# neural_network.net
KiCad netlist of a schematic drawn in EAGLE
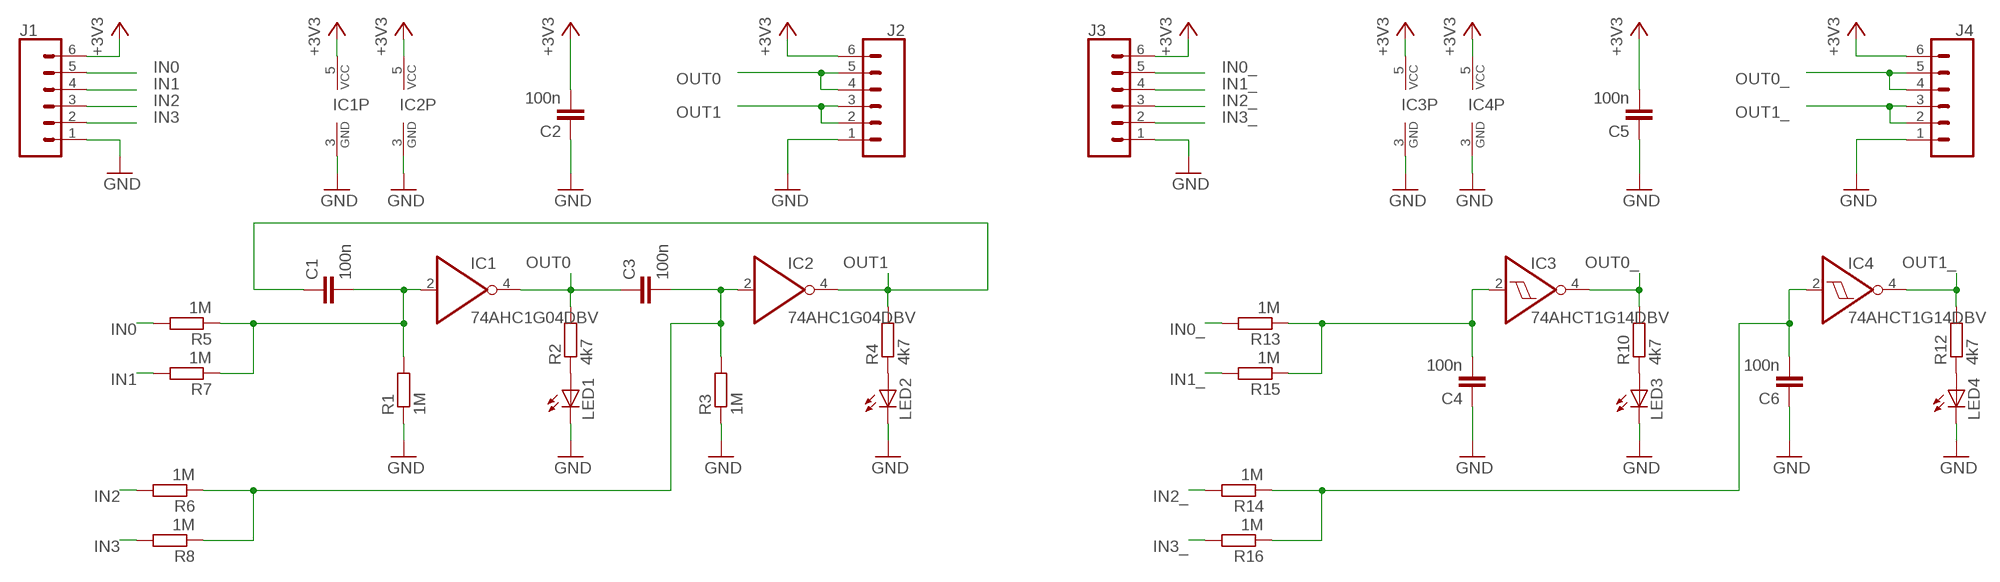
[diagram p0: schematic, sheet 1]

(export (version "E")
  (design (tool "Eeschema 10.0.6"))
  (components
    (comp (ref "C1")
      (value "100n")
      (footprint "eagle-import:C0805")
      (libsource (lib "eagle-import") (part "C-EUC0805"))
    )
    (comp (ref "C2")
      (value "100n")
      (footprint "eagle-import:C0805")
      (libsource (lib "eagle-import") (part "C-EUC0805"))
    )
    (comp (ref "C3")
      (value "100n")
      (footprint "eagle-import:C0805")
      (libsource (lib "eagle-import") (part "C-EUC0805"))
    )
    (comp (ref "C4")
      (value "100n")
      (footprint "eagle-import:C0805")
      (libsource (lib "eagle-import") (part "C-EUC0805"))
    )
    (comp (ref "C5")
      (value "100n")
      (footprint "eagle-import:C0805")
      (libsource (lib "eagle-import") (part "C-EUC0805"))
    )
    (comp (ref "C6")
      (value "100n")
      (footprint "eagle-import:C0805")
      (libsource (lib "eagle-import") (part "C-EUC0805"))
    )
    (comp (ref "IC1")
      (value "74AHC1G04DBV")
      (footprint "eagle-import:SOT23-5")
      (libsource (lib "eagle-import") (part "741G04DBVAHC"))
    )
    (comp (ref "IC2")
      (value "74AHC1G04DBV")
      (footprint "eagle-import:SOT23-5")
      (libsource (lib "eagle-import") (part "741G04DBVAHC"))
    )
    (comp (ref "IC3")
      (value "74AHCT1G14DBV")
      (footprint "eagle-import:SOT23-5")
      (libsource (lib "eagle-import") (part "741G14DBVAHCT"))
    )
    (comp (ref "IC4")
      (value "74AHCT1G14DBV")
      (footprint "eagle-import:SOT23-5")
      (libsource (lib "eagle-import") (part "741G14DBVAHCT"))
    )
    (comp (ref "J1")
      (value "CONN_06LONGPADS")
      (footprint "eagle-import:1X06_LONGPADS")
      (libsource (lib "eagle-import") (part "CONN_06LONGPADS"))
    )
    (comp (ref "J2")
      (value "CONN_06LONGPADS")
      (footprint "eagle-import:1X06_LONGPADS")
      (libsource (lib "eagle-import") (part "CONN_06LONGPADS"))
    )
    (comp (ref "J3")
      (value "CONN_06LONGPADS")
      (footprint "eagle-import:1X06_LONGPADS")
      (libsource (lib "eagle-import") (part "CONN_06LONGPADS"))
    )
    (comp (ref "J4")
      (value "CONN_06LONGPADS")
      (footprint "eagle-import:1X06_LONGPADS")
      (libsource (lib "eagle-import") (part "CONN_06LONGPADS"))
    )
    (comp (ref "LED1")
      (value "LEDCHIPLED_1206")
      (footprint "eagle-import:CHIPLED_1206")
      (libsource (lib "eagle-import") (part "LEDCHIPLED_1206"))
    )
    (comp (ref "LED2")
      (value "LEDCHIPLED_1206")
      (footprint "eagle-import:CHIPLED_1206")
      (libsource (lib "eagle-import") (part "LEDCHIPLED_1206"))
    )
    (comp (ref "LED3")
      (value "LEDCHIPLED_1206")
      (footprint "eagle-import:CHIPLED_1206")
      (libsource (lib "eagle-import") (part "LEDCHIPLED_1206"))
    )
    (comp (ref "LED4")
      (value "LEDCHIPLED_1206")
      (footprint "eagle-import:CHIPLED_1206")
      (libsource (lib "eagle-import") (part "LEDCHIPLED_1206"))
    )
    (comp (ref "R1")
      (value "1M")
      (footprint "eagle-import:M0805")
      (libsource (lib "eagle-import") (part "R-EU_M0805"))
    )
    (comp (ref "R2")
      (value "4k7")
      (footprint "eagle-import:M0805")
      (libsource (lib "eagle-import") (part "R-EU_M0805"))
    )
    (comp (ref "R3")
      (value "1M")
      (footprint "eagle-import:M0805")
      (libsource (lib "eagle-import") (part "R-EU_M0805"))
    )
    (comp (ref "R4")
      (value "4k7")
      (footprint "eagle-import:M0805")
      (libsource (lib "eagle-import") (part "R-EU_M0805"))
    )
    (comp (ref "R5")
      (value "1M")
      (footprint "eagle-import:M0805")
      (libsource (lib "eagle-import") (part "R-EU_M0805"))
    )
    (comp (ref "R6")
      (value "1M")
      (footprint "eagle-import:M0805")
      (libsource (lib "eagle-import") (part "R-EU_M0805"))
    )
    (comp (ref "R7")
      (value "1M")
      (footprint "eagle-import:M0805")
      (libsource (lib "eagle-import") (part "R-EU_M0805"))
    )
    (comp (ref "R8")
      (value "1M")
      (footprint "eagle-import:M0805")
      (libsource (lib "eagle-import") (part "R-EU_M0805"))
    )
    (comp (ref "R10")
      (value "4k7")
      (footprint "eagle-import:M0805")
      (libsource (lib "eagle-import") (part "R-EU_M0805"))
    )
    (comp (ref "R12")
      (value "4k7")
      (footprint "eagle-import:M0805")
      (libsource (lib "eagle-import") (part "R-EU_M0805"))
    )
    (comp (ref "R13")
      (value "1M")
      (footprint "eagle-import:M0805")
      (libsource (lib "eagle-import") (part "R-EU_M0805"))
    )
    (comp (ref "R14")
      (value "1M")
      (footprint "eagle-import:M0805")
      (libsource (lib "eagle-import") (part "R-EU_M0805"))
    )
    (comp (ref "R15")
      (value "1M")
      (footprint "eagle-import:M0805")
      (libsource (lib "eagle-import") (part "R-EU_M0805"))
    )
    (comp (ref "R16")
      (value "1M")
      (footprint "eagle-import:M0805")
      (libsource (lib "eagle-import") (part "R-EU_M0805"))
    )
  )
  (nets
    (net (code "1") (name "+3V3") (class "Default")
      (node (ref "C2") (pin "2") (pinfunction "2_2") (pintype "passive"))
      (node (ref "C5") (pin "2") (pinfunction "2_2") (pintype "passive"))
      (node (ref "IC1") (pin "5") (pinfunction "VCC_5") (pintype "power_in"))
      (node (ref "IC2") (pin "5") (pinfunction "VCC_5") (pintype "power_in"))
      (node (ref "IC3") (pin "5") (pinfunction "VCC_5") (pintype "power_in"))
      (node (ref "IC4") (pin "5") (pinfunction "VCC_5") (pintype "power_in"))
      (node (ref "J1") (pin "6") (pinfunction "6_6") (pintype "passive"))
      (node (ref "J2") (pin "6") (pinfunction "6_6") (pintype "passive"))
      (node (ref "J3") (pin "6") (pinfunction "6_6") (pintype "passive"))
      (node (ref "J4") (pin "6") (pinfunction "6_6") (pintype "passive"))
    )
    (net (code "2") (name "/IN0") (class "Default")
      (node (ref "J1") (pin "5") (pinfunction "5_5") (pintype "passive"))
      (node (ref "R5") (pin "2") (pinfunction "2_2") (pintype "passive"))
    )
    (net (code "3") (name "/IN0_") (class "Default")
      (node (ref "J3") (pin "5") (pinfunction "5_5") (pintype "passive"))
      (node (ref "R13") (pin "2") (pinfunction "2_2") (pintype "passive"))
    )
    (net (code "4") (name "/IN1") (class "Default")
      (node (ref "J1") (pin "4") (pinfunction "4_4") (pintype "passive"))
      (node (ref "R7") (pin "2") (pinfunction "2_2") (pintype "passive"))
    )
    (net (code "5") (name "/IN1_") (class "Default")
      (node (ref "J3") (pin "4") (pinfunction "4_4") (pintype "passive"))
      (node (ref "R15") (pin "2") (pinfunction "2_2") (pintype "passive"))
    )
    (net (code "6") (name "/IN2") (class "Default")
      (node (ref "J1") (pin "3") (pinfunction "3_3") (pintype "passive"))
      (node (ref "R6") (pin "2") (pinfunction "2_2") (pintype "passive"))
    )
    (net (code "7") (name "/IN2_") (class "Default")
      (node (ref "J3") (pin "3") (pinfunction "3_3") (pintype "passive"))
      (node (ref "R14") (pin "2") (pinfunction "2_2") (pintype "passive"))
    )
    (net (code "8") (name "/IN3") (class "Default")
      (node (ref "J1") (pin "2") (pinfunction "2_2") (pintype "passive"))
      (node (ref "R8") (pin "2") (pinfunction "2_2") (pintype "passive"))
    )
    (net (code "9") (name "/IN3_") (class "Default")
      (node (ref "J3") (pin "2") (pinfunction "2_2") (pintype "passive"))
      (node (ref "R16") (pin "2") (pinfunction "2_2") (pintype "passive"))
    )
    (net (code "10") (name "/OUT0") (class "Default")
      (node (ref "C3") (pin "1") (pinfunction "1_1") (pintype "passive"))
      (node (ref "IC1") (pin "4") (pinfunction "O_4") (pintype "output"))
      (node (ref "J2") (pin "4") (pinfunction "4_4") (pintype "passive"))
      (node (ref "J2") (pin "5") (pinfunction "5_5") (pintype "passive"))
      (node (ref "R2") (pin "2") (pinfunction "2_2") (pintype "passive"))
    )
    (net (code "11") (name "/OUT0_") (class "Default")
      (node (ref "IC3") (pin "4") (pinfunction "O_4") (pintype "output"))
      (node (ref "J4") (pin "4") (pinfunction "4_4") (pintype "passive"))
      (node (ref "J4") (pin "5") (pinfunction "5_5") (pintype "passive"))
      (node (ref "R10") (pin "2") (pinfunction "2_2") (pintype "passive"))
    )
    (net (code "12") (name "/OUT1") (class "Default")
      (node (ref "C1") (pin "1") (pinfunction "1_1") (pintype "passive"))
      (node (ref "IC2") (pin "4") (pinfunction "O_4") (pintype "output"))
      (node (ref "J2") (pin "2") (pinfunction "2_2") (pintype "passive"))
      (node (ref "J2") (pin "3") (pinfunction "3_3") (pintype "passive"))
      (node (ref "R4") (pin "2") (pinfunction "2_2") (pintype "passive"))
    )
    (net (code "13") (name "/OUT1_") (class "Default")
      (node (ref "IC4") (pin "4") (pinfunction "O_4") (pintype "output"))
      (node (ref "J4") (pin "2") (pinfunction "2_2") (pintype "passive"))
      (node (ref "J4") (pin "3") (pinfunction "3_3") (pintype "passive"))
      (node (ref "R12") (pin "2") (pinfunction "2_2") (pintype "passive"))
    )
    (net (code "14") (name "GND") (class "Default")
      (node (ref "C2") (pin "1") (pinfunction "1_1") (pintype "passive"))
      (node (ref "C4") (pin "1") (pinfunction "1_1") (pintype "passive"))
      (node (ref "C5") (pin "1") (pinfunction "1_1") (pintype "passive"))
      (node (ref "C6") (pin "1") (pinfunction "1_1") (pintype "passive"))
      (node (ref "IC1") (pin "3") (pinfunction "GND_3") (pintype "power_in"))
      (node (ref "IC2") (pin "3") (pinfunction "GND_3") (pintype "power_in"))
      (node (ref "IC3") (pin "3") (pinfunction "GND_3") (pintype "power_in"))
      (node (ref "IC4") (pin "3") (pinfunction "GND_3") (pintype "power_in"))
      (node (ref "J1") (pin "1") (pinfunction "1_1") (pintype "passive"))
      (node (ref "J2") (pin "1") (pinfunction "1_1") (pintype "passive"))
      (node (ref "J3") (pin "1") (pinfunction "1_1") (pintype "passive"))
      (node (ref "J4") (pin "1") (pinfunction "1_1") (pintype "passive"))
      (node (ref "LED1") (pin "C") (pinfunction "C_C") (pintype "passive"))
      (node (ref "LED2") (pin "C") (pinfunction "C_C") (pintype "passive"))
      (node (ref "LED3") (pin "C") (pinfunction "C_C") (pintype "passive"))
      (node (ref "LED4") (pin "C") (pinfunction "C_C") (pintype "passive"))
      (node (ref "R1") (pin "1") (pinfunction "1_1") (pintype "passive"))
      (node (ref "R3") (pin "1") (pinfunction "1_1") (pintype "passive"))
    )
    (net (code "15") (name "Net-(IC1A-I)") (class "Default")
      (node (ref "C1") (pin "2") (pinfunction "2_2") (pintype "passive"))
      (node (ref "IC1") (pin "2") (pinfunction "I_2") (pintype "input"))
      (node (ref "R1") (pin "2") (pinfunction "2_2") (pintype "passive"))
      (node (ref "R5") (pin "1") (pinfunction "1_1") (pintype "passive"))
      (node (ref "R7") (pin "1") (pinfunction "1_1") (pintype "passive"))
    )
    (net (code "16") (name "Net-(IC2A-I)") (class "Default")
      (node (ref "C3") (pin "2") (pinfunction "2_2") (pintype "passive"))
      (node (ref "IC2") (pin "2") (pinfunction "I_2") (pintype "input"))
      (node (ref "R3") (pin "2") (pinfunction "2_2") (pintype "passive"))
      (node (ref "R6") (pin "1") (pinfunction "1_1") (pintype "passive"))
      (node (ref "R8") (pin "1") (pinfunction "1_1") (pintype "passive"))
    )
    (net (code "17") (name "Net-(IC3A-I)") (class "Default")
      (node (ref "C4") (pin "2") (pinfunction "2_2") (pintype "passive"))
      (node (ref "IC3") (pin "2") (pinfunction "I_2") (pintype "input"))
      (node (ref "R13") (pin "1") (pinfunction "1_1") (pintype "passive"))
      (node (ref "R15") (pin "1") (pinfunction "1_1") (pintype "passive"))
    )
    (net (code "18") (name "Net-(IC4A-I)") (class "Default")
      (node (ref "C6") (pin "2") (pinfunction "2_2") (pintype "passive"))
      (node (ref "IC4") (pin "2") (pinfunction "I_2") (pintype "input"))
      (node (ref "R14") (pin "1") (pinfunction "1_1") (pintype "passive"))
      (node (ref "R16") (pin "1") (pinfunction "1_1") (pintype "passive"))
    )
    (net (code "19") (name "Net-(LED1-PadA)") (class "Default")
      (node (ref "LED1") (pin "A") (pinfunction "A_A") (pintype "passive"))
      (node (ref "R2") (pin "1") (pinfunction "1_1") (pintype "passive"))
    )
    (net (code "20") (name "Net-(LED2-PadA)") (class "Default")
      (node (ref "LED2") (pin "A") (pinfunction "A_A") (pintype "passive"))
      (node (ref "R4") (pin "1") (pinfunction "1_1") (pintype "passive"))
    )
    (net (code "21") (name "Net-(LED3-PadA)") (class "Default")
      (node (ref "LED3") (pin "A") (pinfunction "A_A") (pintype "passive"))
      (node (ref "R10") (pin "1") (pinfunction "1_1") (pintype "passive"))
    )
    (net (code "22") (name "Net-(LED4-PadA)") (class "Default")
      (node (ref "LED4") (pin "A") (pinfunction "A_A") (pintype "passive"))
      (node (ref "R12") (pin "1") (pinfunction "1_1") (pintype "passive"))
    )
  )
)
